# DS18B20.net
KiCad netlist of a schematic drawn in Altium Designer
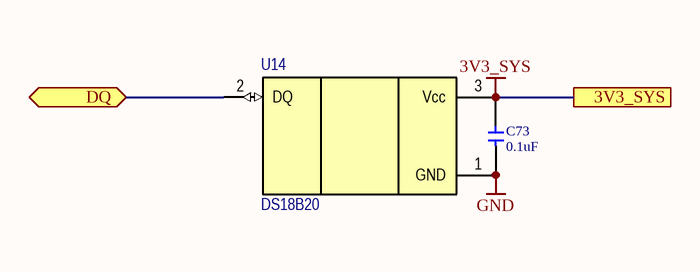
[diagram p0: DS18B20.SchDoc]

(export (version "E")
  (design (tool "Eeschema 10.0.6"))
  (components
    (comp (ref "C73")
      (value "0.1uF")
      (footprint "CERCAP 0402")
      (description "Capacitor")
      (fields (field (name "VOLTAGE") "50V") (field (name "Comment") "CERCAP 0402 0.1uF 50V X7R"))
      (libsource (lib "!main") (part "!Capacitor"))
    )
    (comp (ref "U14")
      (value "DS18B20")
      (footprint "TO-92")
      (description "Temp")
      (libsource (lib "sensors") (part "DS18B20"))
    )
  )
  (nets
    (net (code "1") (name "/DQ") (class "Default")
      (node (ref "U14") (pin "2") (pinfunction "DQ_2") (pintype "bidirectional"))
    )
    (net (code "2") (name "3V3_SYS") (class "Default")
      (node (ref "C73") (pin "2") (pintype "passive"))
      (node (ref "U14") (pin "3") (pinfunction "Vcc_3") (pintype "power_in"))
    )
    (net (code "3") (name "GND") (class "Default")
      (node (ref "C73") (pin "1") (pintype "passive"))
      (node (ref "U14") (pin "1") (pinfunction "GND_1") (pintype "power_in"))
    )
  )
)
